# TEMPERATURE_SENSOR.net
KiCad netlist of a schematic drawn in Altium Designer
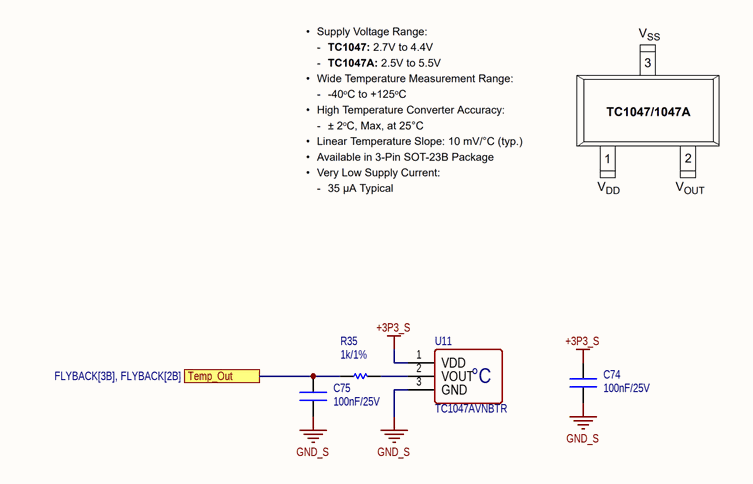
[diagram p0: TEMPERATURE_SENSOR.SchDoc]

(export (version "E")
  (design (tool "Eeschema 10.0.6"))
  (components
    (comp (ref "C74")
      (value "100nF/25V")
      (footprint "CN-SMD-0603")
      (description "CAP CER 0.1UF 25V X7R 0603")
      (libsource (lib "Library") (part "CN"))
    )
    (comp (ref "C75")
      (value "100nF/25V")
      (footprint "CN-SMD-0603")
      (description "CAP CER 0.1UF 25V X7R 0603")
      (libsource (lib "Library") (part "CN"))
    )
    (comp (ref "R35")
      (value "1k/1%")
      (footprint "RES-SMD-0603")
      (description "RES SMD 1K OHM 1% 1/10W 0603")
      (fields
        (field (name "MANUFACTURER") "Generic Components")
        (field (name "PUBLISHER") "Altium Hobart Technology Centre")
      )
      (libsource (lib "Library") (part "Res-SMD"))
    )
    (comp (ref "U11")
      (value "TC1047AVNBTR")
      (footprint "SOT23-132")
      (description "SENSOR ANALOG -40C-125C SOT23-3")
      (libsource (lib "Library") (part "TC1047AVNBTR"))
    )
  )
  (nets
    (net (code "1") (name "+3P3_S") (class "Default")
      (node (ref "C74") (pin "2") (pinfunction "2_2") (pintype "passive"))
      (node (ref "U11") (pin "1") (pinfunction "VDD_1") (pintype "passive"))
    )
    (net (code "2") (name "/Temp_Out") (class "Default")
      (node (ref "C75") (pin "2") (pinfunction "2_2") (pintype "passive"))
      (node (ref "R35") (pin "1") (pinfunction "1_1") (pintype "passive"))
    )
    (net (code "3") (name "GND_S") (class "Default")
      (node (ref "C74") (pin "1") (pinfunction "1_1") (pintype "passive"))
      (node (ref "C75") (pin "1") (pinfunction "1_1") (pintype "passive"))
      (node (ref "U11") (pin "3") (pinfunction "GND_3") (pintype "passive"))
    )
    (net (code "4") (name "Net-(U11-VOUT)") (class "Default")
      (node (ref "R35") (pin "2") (pinfunction "2_2") (pintype "passive"))
      (node (ref "U11") (pin "2") (pinfunction "VOUT_2") (pintype "passive"))
    )
  )
)
